# nRF52810_qcaa.net
KiCad netlist of a schematic drawn in EAGLE
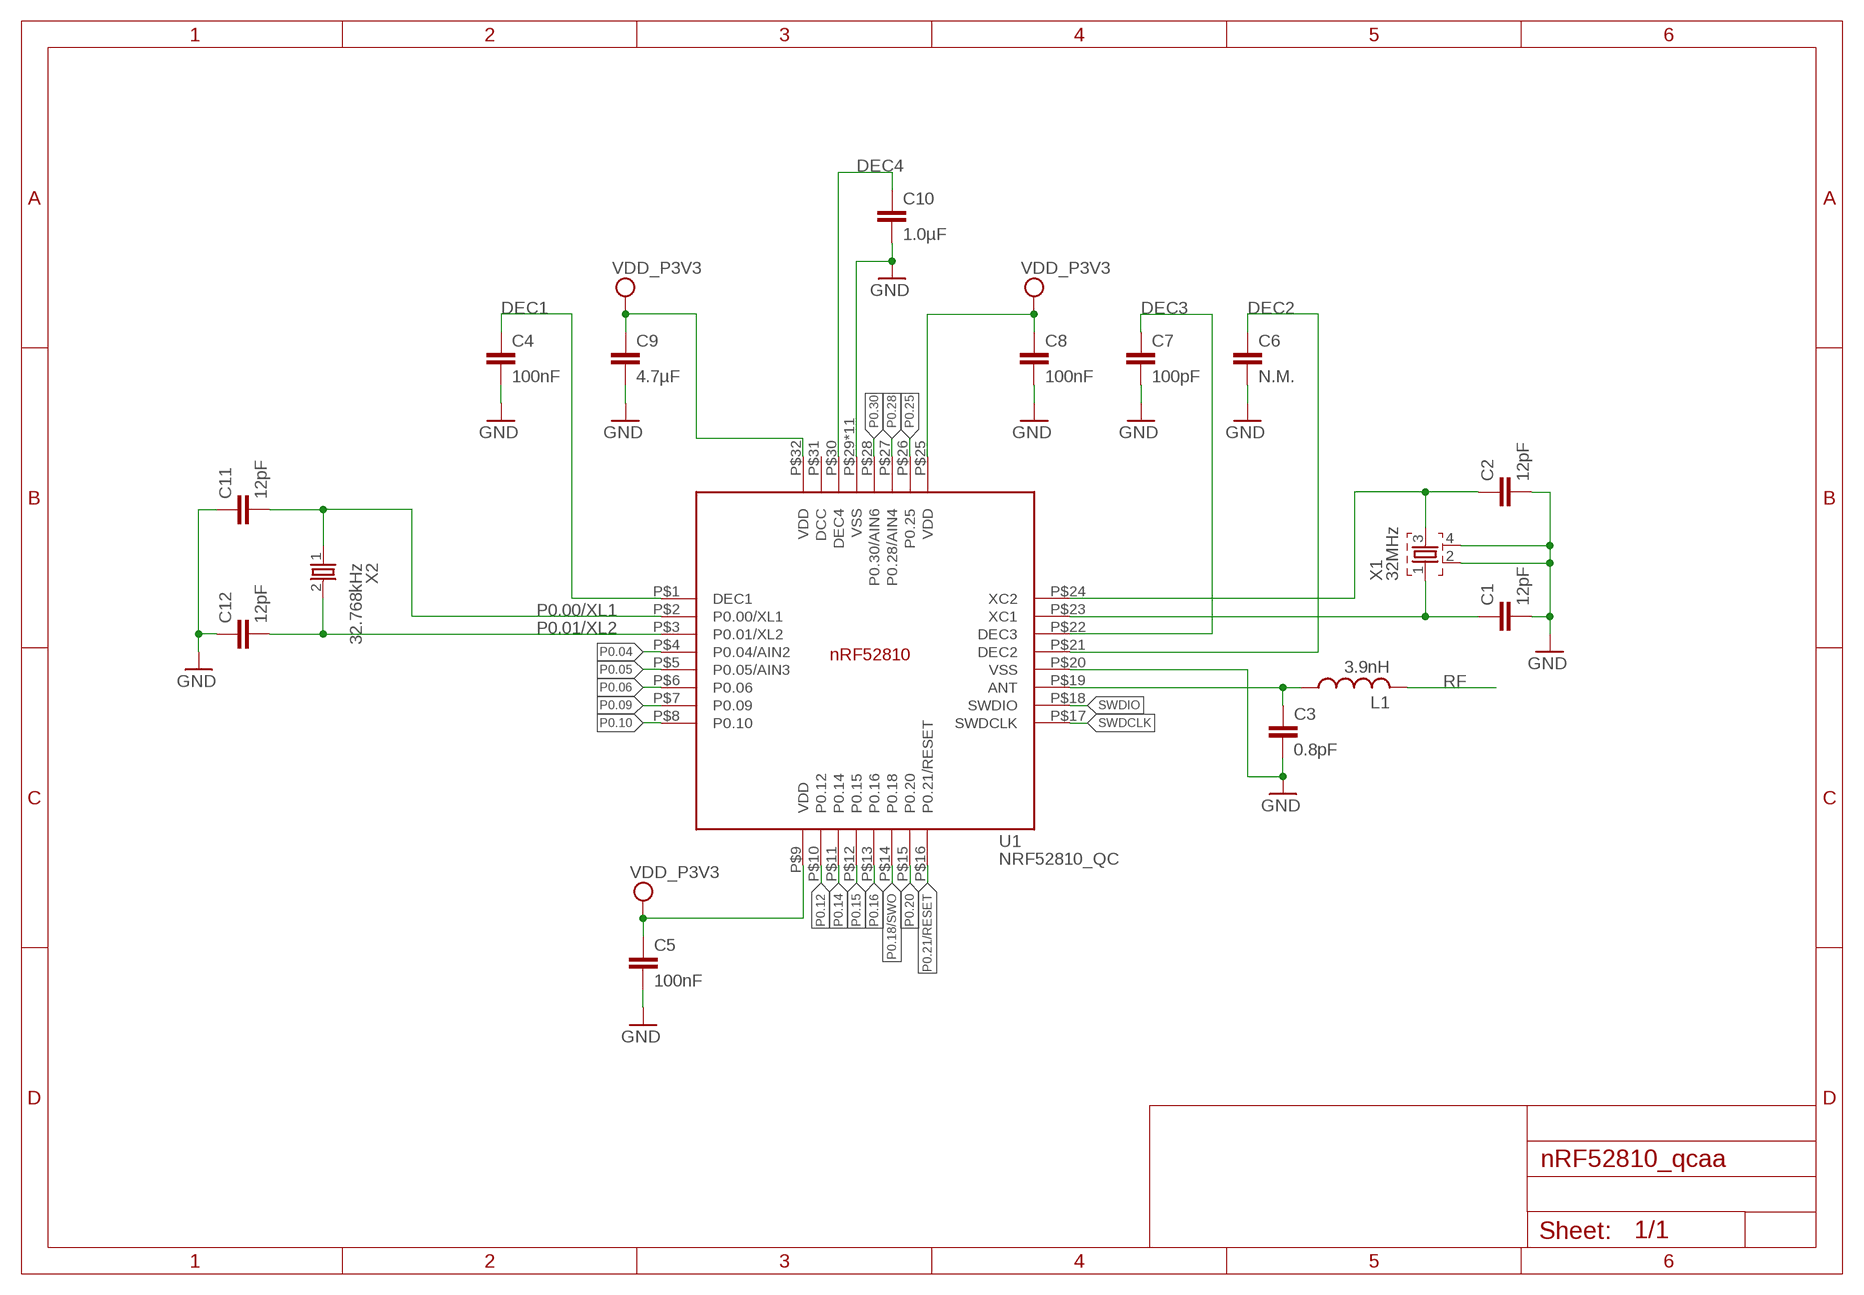
[diagram p0: schematic, sheet 1]

(export (version "E")
  (design (tool "Eeschema 10.0.6"))
  (components
    (comp (ref "C1")
      (value "12pF")
      (footprint "eagle-import:RESC0402_N")
      (libsource (lib "eagle-import") (part "CAPACITOR_0402_N"))
    )
    (comp (ref "C2")
      (value "12pF")
      (footprint "eagle-import:RESC0402_N")
      (libsource (lib "eagle-import") (part "CAPACITOR_0402_N"))
    )
    (comp (ref "C3")
      (value "0.8pF")
      (footprint "eagle-import:RESC0402_N")
      (libsource (lib "eagle-import") (part "CAPACITOR_0402_N"))
    )
    (comp (ref "C4")
      (value "100nF")
      (footprint "eagle-import:RESC0402_N")
      (libsource (lib "eagle-import") (part "CAPACITOR_0402_N"))
    )
    (comp (ref "C5")
      (value "100nF")
      (footprint "eagle-import:RESC0402_N")
      (libsource (lib "eagle-import") (part "CAPACITOR_0402_N"))
    )
    (comp (ref "C6")
      (value "N.M.")
      (footprint "eagle-import:RESC0402_N")
      (libsource (lib "eagle-import") (part "CAPACITOR_0402_N"))
    )
    (comp (ref "C7")
      (value "100pF")
      (footprint "eagle-import:RESC0402_N")
      (libsource (lib "eagle-import") (part "CAPACITOR_0402_N"))
    )
    (comp (ref "C8")
      (value "100nF")
      (footprint "eagle-import:RESC0402_N")
      (libsource (lib "eagle-import") (part "CAPACITOR_0402_N"))
    )
    (comp (ref "C9")
      (value "4.7µF")
      (footprint "eagle-import:RESC0603_N")
      (libsource (lib "eagle-import") (part "CAPACITOR_0603_N"))
    )
    (comp (ref "C10")
      (value "1.0µF")
      (footprint "eagle-import:RESC0603_N")
      (libsource (lib "eagle-import") (part "CAPACITOR_0603_N"))
    )
    (comp (ref "C11")
      (value "12pF")
      (footprint "eagle-import:RESC0402_N")
      (libsource (lib "eagle-import") (part "CAPACITOR_0402_N"))
    )
    (comp (ref "C12")
      (value "12pF")
      (footprint "eagle-import:RESC0402_N")
      (libsource (lib "eagle-import") (part "CAPACITOR_0402_N"))
    )
    (comp (ref "L1")
      (value "3.9nH")
      (footprint "eagle-import:RESC0402_N")
      (libsource (lib "eagle-import") (part "INDUCTOR_0402_N"))
    )
    (comp (ref "U1")
      (value "NRF52810_QC")
      (footprint "eagle-import:QFN50P500X500X90-32_N")
      (libsource (lib "eagle-import") (part "NRF52810_QC"))
    )
    (comp (ref "X1")
      (value "32MHz")
      (footprint "eagle-import:BT-XTAL_2016_N")
      (libsource (lib "eagle-import") (part "XTAL_32MHZ"))
    )
    (comp (ref "X2")
      (value "32.768kHz")
      (footprint "eagle-import:XTAL_3215_N")
      (libsource (lib "eagle-import") (part "XTAL_32KHZ"))
    )
  )
  (nets
    (net (code "1") (name "/DEC1") (class "Default")
      (node (ref "C4") (pin "1") (pinfunction "1_1") (pintype "passive"))
      (node (ref "U1") (pin "P$1") (pinfunction "DEC1_P$1") (pintype "bidirectional"))
    )
    (net (code "2") (name "/DEC2") (class "Default")
      (node (ref "C6") (pin "1") (pinfunction "1_1") (pintype "passive"))
      (node (ref "U1") (pin "P$21") (pinfunction "DEC2_P$21") (pintype "bidirectional"))
    )
    (net (code "3") (name "/DEC3") (class "Default")
      (node (ref "C7") (pin "1") (pinfunction "1_1") (pintype "passive"))
      (node (ref "U1") (pin "P$22") (pinfunction "DEC3_P$22") (pintype "bidirectional"))
    )
    (net (code "4") (name "/DEC4") (class "Default")
      (node (ref "C10") (pin "1") (pinfunction "1_1") (pintype "passive"))
      (node (ref "U1") (pin "P$30") (pinfunction "DEC4_P$30") (pintype "bidirectional"))
    )
    (net (code "5") (name "/P0.00{slash}XL1") (class "Default")
      (node (ref "C11") (pin "2") (pinfunction "2_2") (pintype "passive"))
      (node (ref "U1") (pin "P$2") (pinfunction "P0.00/XL1_P$2") (pintype "bidirectional"))
      (node (ref "X2") (pin "1") (pinfunction "1_1") (pintype "passive"))
    )
    (net (code "6") (name "/P0.01{slash}XL2") (class "Default")
      (node (ref "C12") (pin "2") (pinfunction "2_2") (pintype "passive"))
      (node (ref "U1") (pin "P$3") (pinfunction "P0.01/XL2_P$3") (pintype "bidirectional"))
      (node (ref "X2") (pin "2") (pinfunction "2_2") (pintype "passive"))
    )
    (net (code "7") (name "/RF") (class "Default")
      (node (ref "L1") (pin "2") (pinfunction "2_2") (pintype "passive"))
    )
    (net (code "8") (name "GND") (class "Default")
      (node (ref "C1") (pin "2") (pinfunction "2_2") (pintype "passive"))
      (node (ref "C10") (pin "2") (pinfunction "2_2") (pintype "passive"))
      (node (ref "C11") (pin "1") (pinfunction "1_1") (pintype "passive"))
      (node (ref "C12") (pin "1") (pinfunction "1_1") (pintype "passive"))
      (node (ref "C2") (pin "2") (pinfunction "2_2") (pintype "passive"))
      (node (ref "C3") (pin "2") (pinfunction "2_2") (pintype "passive"))
      (node (ref "C4") (pin "2") (pinfunction "2_2") (pintype "passive"))
      (node (ref "C5") (pin "2") (pinfunction "2_2") (pintype "passive"))
      (node (ref "C6") (pin "2") (pinfunction "2_2") (pintype "passive"))
      (node (ref "C7") (pin "2") (pinfunction "2_2") (pintype "passive"))
      (node (ref "C8") (pin "2") (pinfunction "2_2") (pintype "passive"))
      (node (ref "C9") (pin "2") (pinfunction "2_2") (pintype "passive"))
      (node (ref "U1") (pin "P$20") (pinfunction "VSS_P$20") (pintype "bidirectional"))
      (node (ref "U1") (pin "P$29") (pinfunction "VSS_P$29") (pintype "bidirectional"))
      (node (ref "U1") (pin "P$33") (pinfunction "VSS_P$33") (pintype "bidirectional"))
      (node (ref "U1") (pin "P$34") (pinfunction "VSS_P$34") (pintype "bidirectional"))
      (node (ref "U1") (pin "P$35") (pinfunction "VSS_P$35") (pintype "bidirectional"))
      (node (ref "U1") (pin "P$36") (pinfunction "VSS_P$36") (pintype "bidirectional"))
      (node (ref "U1") (pin "P$37") (pinfunction "VSS_P$37") (pintype "bidirectional"))
      (node (ref "U1") (pin "P$38") (pinfunction "VSS_P$38") (pintype "bidirectional"))
      (node (ref "U1") (pin "P$39") (pinfunction "VSS_P$39") (pintype "bidirectional"))
      (node (ref "U1") (pin "P$40") (pinfunction "VSS_P$40") (pintype "bidirectional"))
      (node (ref "U1") (pin "P$41") (pinfunction "VSS_P$41") (pintype "bidirectional"))
      (node (ref "U1") (pin "P$42") (pinfunction "VSS_P$42") (pintype "bidirectional"))
      (node (ref "X1") (pin "2") (pinfunction "2_2") (pintype "passive"))
      (node (ref "X1") (pin "4") (pinfunction "4_4") (pintype "passive"))
    )
    (net (code "9") (name "Net-(U1-ANT)") (class "Default")
      (node (ref "C3") (pin "1") (pinfunction "1_1") (pintype "passive"))
      (node (ref "L1") (pin "1") (pinfunction "1_1") (pintype "passive"))
      (node (ref "U1") (pin "P$19") (pinfunction "ANT_P$19") (pintype "bidirectional"))
    )
    (net (code "10") (name "Net-(U1-XC1)") (class "Default")
      (node (ref "C1") (pin "1") (pinfunction "1_1") (pintype "passive"))
      (node (ref "U1") (pin "P$23") (pinfunction "XC1_P$23") (pintype "bidirectional"))
      (node (ref "X1") (pin "1") (pinfunction "1_1") (pintype "passive"))
    )
    (net (code "11") (name "Net-(U1-XC2)") (class "Default")
      (node (ref "C2") (pin "1") (pinfunction "1_1") (pintype "passive"))
      (node (ref "U1") (pin "P$24") (pinfunction "XC2_P$24") (pintype "bidirectional"))
      (node (ref "X1") (pin "3") (pinfunction "3_3") (pintype "passive"))
    )
    (net (code "12") (name "P0.04") (class "Default")
      (node (ref "U1") (pin "P$4") (pinfunction "P0.04/AIN2_P$4") (pintype "bidirectional"))
    )
    (net (code "13") (name "P0.05") (class "Default")
      (node (ref "U1") (pin "P$5") (pinfunction "P0.05/AIN3_P$5") (pintype "bidirectional"))
    )
    (net (code "14") (name "P0.06") (class "Default")
      (node (ref "U1") (pin "P$6") (pinfunction "P0.06_P$6") (pintype "bidirectional"))
    )
    (net (code "15") (name "P0.09") (class "Default")
      (node (ref "U1") (pin "P$7") (pinfunction "P0.09_P$7") (pintype "bidirectional"))
    )
    (net (code "16") (name "P0.10") (class "Default")
      (node (ref "U1") (pin "P$8") (pinfunction "P0.10_P$8") (pintype "bidirectional"))
    )
    (net (code "17") (name "P0.12") (class "Default")
      (node (ref "U1") (pin "P$10") (pinfunction "P0.12_P$10") (pintype "bidirectional"))
    )
    (net (code "18") (name "P0.14") (class "Default")
      (node (ref "U1") (pin "P$11") (pinfunction "P0.14_P$11") (pintype "bidirectional"))
    )
    (net (code "19") (name "P0.15") (class "Default")
      (node (ref "U1") (pin "P$12") (pinfunction "P0.15_P$12") (pintype "bidirectional"))
    )
    (net (code "20") (name "P0.16") (class "Default")
      (node (ref "U1") (pin "P$13") (pinfunction "P0.16_P$13") (pintype "bidirectional"))
    )
    (net (code "21") (name "P0.18{slash}SWO") (class "Default")
      (node (ref "U1") (pin "P$14") (pinfunction "P0.18_P$14") (pintype "bidirectional"))
    )
    (net (code "22") (name "P0.20") (class "Default")
      (node (ref "U1") (pin "P$15") (pinfunction "P0.20_P$15") (pintype "bidirectional"))
    )
    (net (code "23") (name "P0.21{slash}RESET") (class "Default")
      (node (ref "U1") (pin "P$16") (pinfunction "P0.21/RESET_P$16") (pintype "bidirectional"))
    )
    (net (code "24") (name "P0.25") (class "Default")
      (node (ref "U1") (pin "P$26") (pinfunction "P0.25_P$26") (pintype "bidirectional"))
    )
    (net (code "25") (name "P0.28") (class "Default")
      (node (ref "U1") (pin "P$27") (pinfunction "P0.28/AIN4_P$27") (pintype "bidirectional"))
    )
    (net (code "26") (name "P0.30") (class "Default")
      (node (ref "U1") (pin "P$28") (pinfunction "P0.30/AIN6_P$28") (pintype "bidirectional"))
    )
    (net (code "27") (name "SWDCLK") (class "Default")
      (node (ref "U1") (pin "P$17") (pinfunction "SWDCLK_P$17") (pintype "bidirectional"))
    )
    (net (code "28") (name "SWDIO") (class "Default")
      (node (ref "U1") (pin "P$18") (pinfunction "SWDIO_P$18") (pintype "bidirectional"))
    )
    (net (code "29") (name "VDD_P3V3") (class "Default")
      (node (ref "C5") (pin "1") (pinfunction "1_1") (pintype "passive"))
      (node (ref "C8") (pin "1") (pinfunction "1_1") (pintype "passive"))
      (node (ref "C9") (pin "1") (pinfunction "1_1") (pintype "passive"))
      (node (ref "U1") (pin "P$25") (pinfunction "VDD_P$25") (pintype "bidirectional"))
      (node (ref "U1") (pin "P$32") (pinfunction "VDD_P$32") (pintype "bidirectional"))
      (node (ref "U1") (pin "P$9") (pinfunction "VDD_P$9") (pintype "bidirectional"))
    )
    (net (code "30") (name "unconnected-(U1-DCC-PadP$31)") (class "Default")
      (node (ref "U1") (pin "P$31") (pinfunction "DCC_P$31") (pintype "bidirectional"))
    )
  )
)
